# Open_EVI.net
KiCad netlist of a schematic drawn in EAGLE
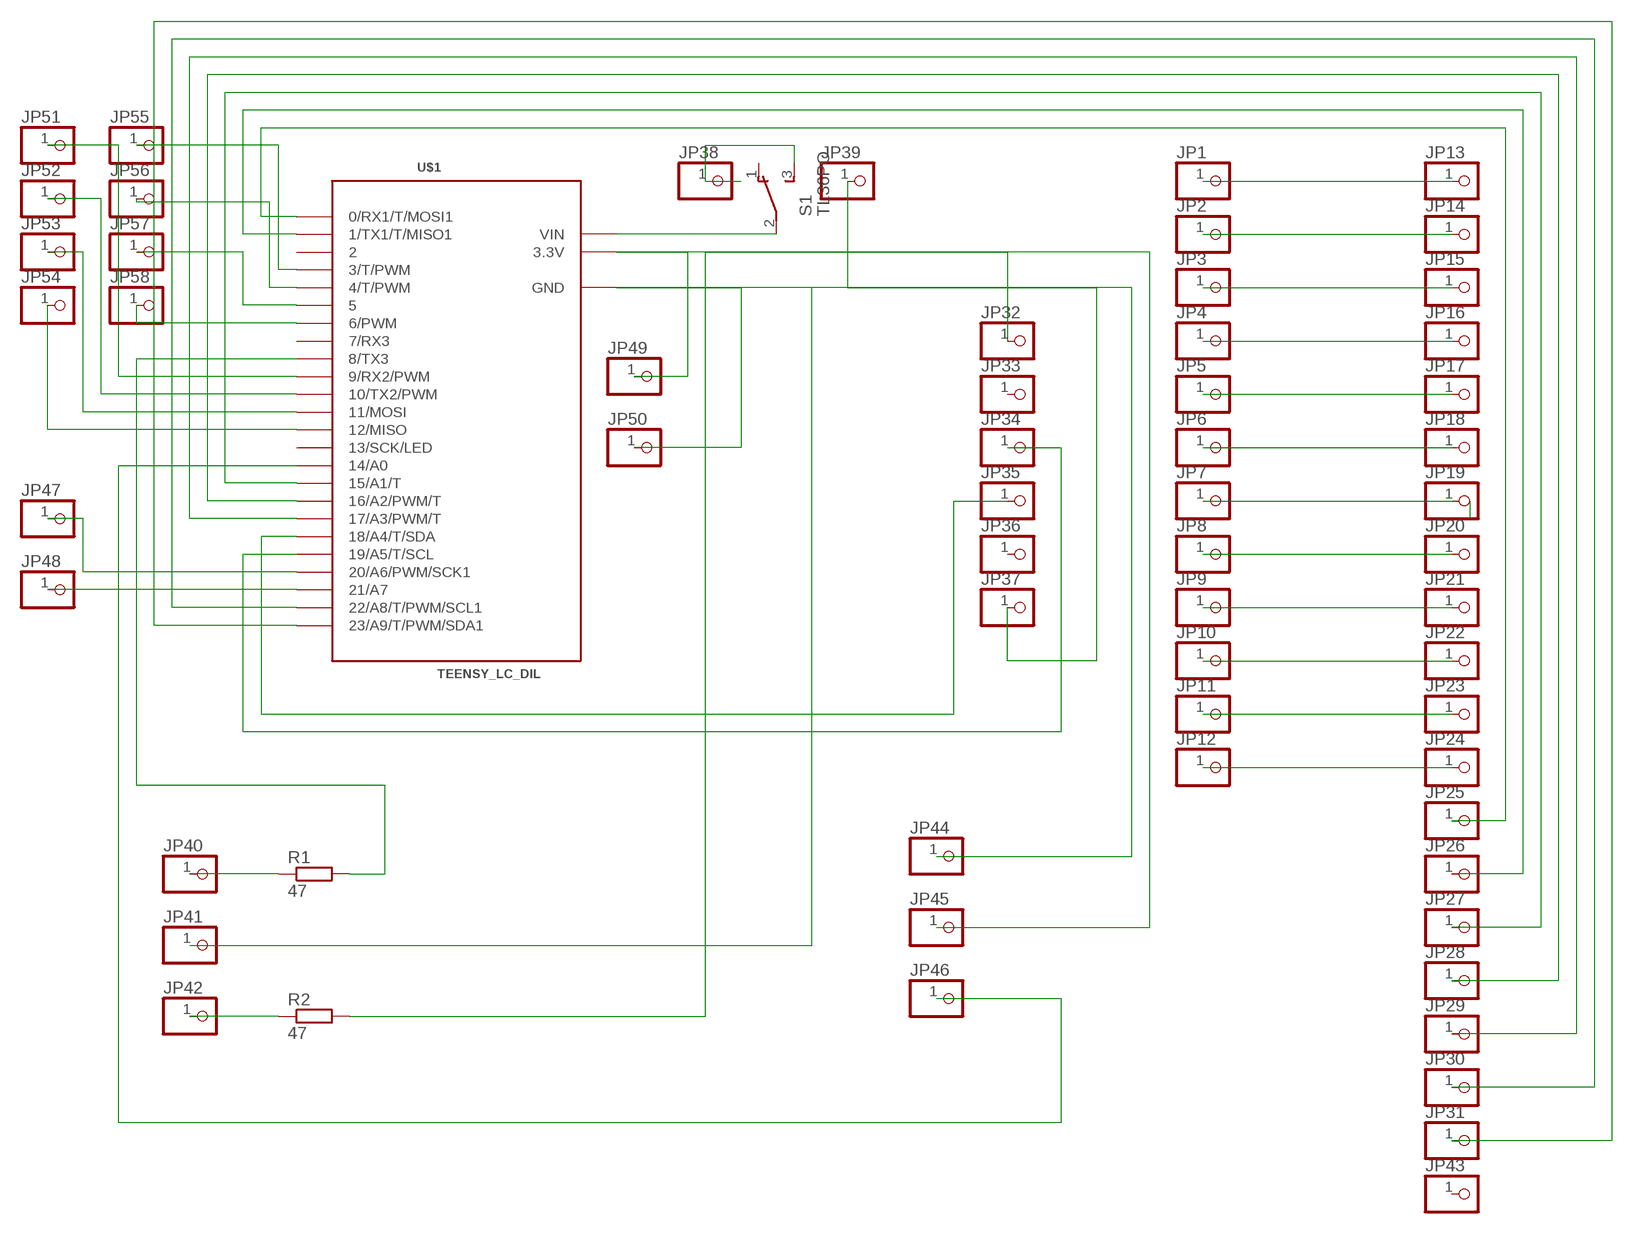
[diagram p0: schematic, sheet 1]

(export (version "E")
  (design (tool "Eeschema 10.0.6"))
  (components
    (comp (ref "JP1")
      (value "PINHD-1X1")
      (footprint "eagle-import:1X01")
      (libsource (lib "eagle-import") (part "PINHD-1X1"))
    )
    (comp (ref "JP2")
      (value "PINHD-1X1")
      (footprint "eagle-import:1X01")
      (libsource (lib "eagle-import") (part "PINHD-1X1"))
    )
    (comp (ref "JP3")
      (value "PINHD-1X1")
      (footprint "eagle-import:1X01")
      (libsource (lib "eagle-import") (part "PINHD-1X1"))
    )
    (comp (ref "JP4")
      (value "PINHD-1X1")
      (footprint "eagle-import:1X01")
      (libsource (lib "eagle-import") (part "PINHD-1X1"))
    )
    (comp (ref "JP5")
      (value "PINHD-1X1")
      (footprint "eagle-import:1X01")
      (libsource (lib "eagle-import") (part "PINHD-1X1"))
    )
    (comp (ref "JP6")
      (value "PINHD-1X1")
      (footprint "eagle-import:1X01")
      (libsource (lib "eagle-import") (part "PINHD-1X1"))
    )
    (comp (ref "JP7")
      (value "PINHD-1X1")
      (footprint "eagle-import:1X01")
      (libsource (lib "eagle-import") (part "PINHD-1X1"))
    )
    (comp (ref "JP8")
      (value "PINHD-1X1")
      (footprint "eagle-import:1X01")
      (libsource (lib "eagle-import") (part "PINHD-1X1"))
    )
    (comp (ref "JP9")
      (value "PINHD-1X1")
      (footprint "eagle-import:1X01")
      (libsource (lib "eagle-import") (part "PINHD-1X1"))
    )
    (comp (ref "JP10")
      (value "PINHD-1X1")
      (footprint "eagle-import:1X01")
      (libsource (lib "eagle-import") (part "PINHD-1X1"))
    )
    (comp (ref "JP11")
      (value "PINHD-1X1")
      (footprint "eagle-import:1X01")
      (libsource (lib "eagle-import") (part "PINHD-1X1"))
    )
    (comp (ref "JP12")
      (value "PINHD-1X1")
      (footprint "eagle-import:1X01")
      (libsource (lib "eagle-import") (part "PINHD-1X1"))
    )
    (comp (ref "JP13")
      (value "PINHD-1X1")
      (footprint "eagle-import:1X01")
      (libsource (lib "eagle-import") (part "PINHD-1X1"))
    )
    (comp (ref "JP14")
      (value "PINHD-1X1")
      (footprint "eagle-import:1X01")
      (libsource (lib "eagle-import") (part "PINHD-1X1"))
    )
    (comp (ref "JP15")
      (value "PINHD-1X1")
      (footprint "eagle-import:1X01")
      (libsource (lib "eagle-import") (part "PINHD-1X1"))
    )
    (comp (ref "JP16")
      (value "PINHD-1X1")
      (footprint "eagle-import:1X01")
      (libsource (lib "eagle-import") (part "PINHD-1X1"))
    )
    (comp (ref "JP17")
      (value "PINHD-1X1")
      (footprint "eagle-import:1X01")
      (libsource (lib "eagle-import") (part "PINHD-1X1"))
    )
    (comp (ref "JP18")
      (value "PINHD-1X1")
      (footprint "eagle-import:1X01")
      (libsource (lib "eagle-import") (part "PINHD-1X1"))
    )
    (comp (ref "JP19")
      (value "PINHD-1X1")
      (footprint "eagle-import:1X01")
      (libsource (lib "eagle-import") (part "PINHD-1X1"))
    )
    (comp (ref "JP20")
      (value "PINHD-1X1")
      (footprint "eagle-import:1X01")
      (libsource (lib "eagle-import") (part "PINHD-1X1"))
    )
    (comp (ref "JP21")
      (value "PINHD-1X1")
      (footprint "eagle-import:1X01")
      (libsource (lib "eagle-import") (part "PINHD-1X1"))
    )
    (comp (ref "JP22")
      (value "PINHD-1X1")
      (footprint "eagle-import:1X01")
      (libsource (lib "eagle-import") (part "PINHD-1X1"))
    )
    (comp (ref "JP23")
      (value "PINHD-1X1")
      (footprint "eagle-import:1X01")
      (libsource (lib "eagle-import") (part "PINHD-1X1"))
    )
    (comp (ref "JP24")
      (value "PINHD-1X1")
      (footprint "eagle-import:1X01")
      (libsource (lib "eagle-import") (part "PINHD-1X1"))
    )
    (comp (ref "JP25")
      (value "PINHD-1X1")
      (footprint "eagle-import:1X01")
      (libsource (lib "eagle-import") (part "PINHD-1X1"))
    )
    (comp (ref "JP26")
      (value "PINHD-1X1")
      (footprint "eagle-import:1X01")
      (libsource (lib "eagle-import") (part "PINHD-1X1"))
    )
    (comp (ref "JP27")
      (value "PINHD-1X1")
      (footprint "eagle-import:1X01")
      (libsource (lib "eagle-import") (part "PINHD-1X1"))
    )
    (comp (ref "JP28")
      (value "PINHD-1X1")
      (footprint "eagle-import:1X01")
      (libsource (lib "eagle-import") (part "PINHD-1X1"))
    )
    (comp (ref "JP29")
      (value "PINHD-1X1")
      (footprint "eagle-import:1X01")
      (libsource (lib "eagle-import") (part "PINHD-1X1"))
    )
    (comp (ref "JP30")
      (value "PINHD-1X1")
      (footprint "eagle-import:1X01")
      (libsource (lib "eagle-import") (part "PINHD-1X1"))
    )
    (comp (ref "JP31")
      (value "PINHD-1X1")
      (footprint "eagle-import:1X01")
      (libsource (lib "eagle-import") (part "PINHD-1X1"))
    )
    (comp (ref "JP32")
      (value "PINHD-1X1")
      (footprint "eagle-import:1X01")
      (libsource (lib "eagle-import") (part "PINHD-1X1"))
    )
    (comp (ref "JP33")
      (value "PINHD-1X1")
      (footprint "eagle-import:1X01")
      (libsource (lib "eagle-import") (part "PINHD-1X1"))
    )
    (comp (ref "JP34")
      (value "PINHD-1X1")
      (footprint "eagle-import:1X01")
      (libsource (lib "eagle-import") (part "PINHD-1X1"))
    )
    (comp (ref "JP35")
      (value "PINHD-1X1")
      (footprint "eagle-import:1X01")
      (libsource (lib "eagle-import") (part "PINHD-1X1"))
    )
    (comp (ref "JP36")
      (value "PINHD-1X1")
      (footprint "eagle-import:1X01")
      (libsource (lib "eagle-import") (part "PINHD-1X1"))
    )
    (comp (ref "JP37")
      (value "PINHD-1X1")
      (footprint "eagle-import:1X01")
      (libsource (lib "eagle-import") (part "PINHD-1X1"))
    )
    (comp (ref "JP38")
      (value "PINHD-1X1")
      (footprint "eagle-import:1X01")
      (libsource (lib "eagle-import") (part "PINHD-1X1"))
    )
    (comp (ref "JP39")
      (value "PINHD-1X1")
      (footprint "eagle-import:1X01")
      (libsource (lib "eagle-import") (part "PINHD-1X1"))
    )
    (comp (ref "JP40")
      (value "PINHD-1X1")
      (footprint "eagle-import:1X01")
      (libsource (lib "eagle-import") (part "PINHD-1X1"))
    )
    (comp (ref "JP41")
      (value "PINHD-1X1")
      (footprint "eagle-import:1X01")
      (libsource (lib "eagle-import") (part "PINHD-1X1"))
    )
    (comp (ref "JP42")
      (value "PINHD-1X1")
      (footprint "eagle-import:1X01")
      (libsource (lib "eagle-import") (part "PINHD-1X1"))
    )
    (comp (ref "JP43")
      (value "PINHD-1X1")
      (footprint "eagle-import:1X01")
      (libsource (lib "eagle-import") (part "PINHD-1X1"))
    )
    (comp (ref "JP44")
      (value "PINHD-1X1")
      (footprint "eagle-import:1X01")
      (libsource (lib "eagle-import") (part "PINHD-1X1"))
    )
    (comp (ref "JP45")
      (value "PINHD-1X1")
      (footprint "eagle-import:1X01")
      (libsource (lib "eagle-import") (part "PINHD-1X1"))
    )
    (comp (ref "JP46")
      (value "PINHD-1X1")
      (footprint "eagle-import:1X01")
      (libsource (lib "eagle-import") (part "PINHD-1X1"))
    )
    (comp (ref "JP47")
      (value "PINHD-1X1")
      (footprint "eagle-import:1X01")
      (libsource (lib "eagle-import") (part "PINHD-1X1"))
    )
    (comp (ref "JP48")
      (value "PINHD-1X1")
      (footprint "eagle-import:1X01")
      (libsource (lib "eagle-import") (part "PINHD-1X1"))
    )
    (comp (ref "JP49")
      (value "PINHD-1X1")
      (footprint "eagle-import:1X01")
      (libsource (lib "eagle-import") (part "PINHD-1X1"))
    )
    (comp (ref "JP50")
      (value "PINHD-1X1")
      (footprint "eagle-import:1X01")
      (libsource (lib "eagle-import") (part "PINHD-1X1"))
    )
    (comp (ref "JP51")
      (value "PINHD-1X1")
      (footprint "eagle-import:1X01")
      (libsource (lib "eagle-import") (part "PINHD-1X1"))
    )
    (comp (ref "JP52")
      (value "PINHD-1X1")
      (footprint "eagle-import:1X01")
      (libsource (lib "eagle-import") (part "PINHD-1X1"))
    )
    (comp (ref "JP53")
      (value "PINHD-1X1")
      (footprint "eagle-import:1X01")
      (libsource (lib "eagle-import") (part "PINHD-1X1"))
    )
    (comp (ref "JP54")
      (value "PINHD-1X1")
      (footprint "eagle-import:1X01")
      (libsource (lib "eagle-import") (part "PINHD-1X1"))
    )
    (comp (ref "JP55")
      (value "PINHD-1X1")
      (footprint "eagle-import:1X01")
      (libsource (lib "eagle-import") (part "PINHD-1X1"))
    )
    (comp (ref "JP56")
      (value "PINHD-1X1")
      (footprint "eagle-import:1X01")
      (libsource (lib "eagle-import") (part "PINHD-1X1"))
    )
    (comp (ref "JP57")
      (value "PINHD-1X1")
      (footprint "eagle-import:1X01")
      (libsource (lib "eagle-import") (part "PINHD-1X1"))
    )
    (comp (ref "JP58")
      (value "PINHD-1X1")
      (footprint "eagle-import:1X01")
      (libsource (lib "eagle-import") (part "PINHD-1X1"))
    )
    (comp (ref "R1")
      (value "47")
      (footprint "eagle-import:0207_7")
      (libsource (lib "eagle-import") (part "R-EU_0207/7"))
    )
    (comp (ref "R2")
      (value "47")
      (footprint "eagle-import:0207_7")
      (libsource (lib "eagle-import") (part "R-EU_0207/7"))
    )
    (comp (ref "S1")
      (value "TL36PO")
      (footprint "eagle-import:TL3XPO")
      (libsource (lib "eagle-import") (part "TL36PO"))
    )
    (comp (ref "U$1")
      (value "TEENSY_LC_DIL")
      (footprint "eagle-import:TEENSY_3.0-3.2&LC_DIL")
      (libsource (lib "eagle-import") (part "TEENSY_LC_DIL"))
    )
  )
  (nets
    (net (code "1") (name "Net-(JP1-Pad1)") (class "Default")
      (node (ref "JP1") (pin "1") (pinfunction "1_1") (pintype "passive"))
      (node (ref "JP13") (pin "1") (pinfunction "1_1") (pintype "passive"))
    )
    (net (code "2") (name "Net-(JP10-Pad1)") (class "Default")
      (node (ref "JP10") (pin "1") (pinfunction "1_1") (pintype "passive"))
      (node (ref "JP22") (pin "1") (pinfunction "1_1") (pintype "passive"))
    )
    (net (code "3") (name "Net-(JP11-Pad1)") (class "Default")
      (node (ref "JP11") (pin "1") (pinfunction "1_1") (pintype "passive"))
      (node (ref "JP23") (pin "1") (pinfunction "1_1") (pintype "passive"))
    )
    (net (code "4") (name "Net-(JP12-Pad1)") (class "Default")
      (node (ref "JP12") (pin "1") (pinfunction "1_1") (pintype "passive"))
      (node (ref "JP24") (pin "1") (pinfunction "1_1") (pintype "passive"))
    )
    (net (code "5") (name "Net-(JP14-Pad1)") (class "Default")
      (node (ref "JP14") (pin "1") (pinfunction "1_1") (pintype "passive"))
      (node (ref "JP2") (pin "1") (pinfunction "1_1") (pintype "passive"))
    )
    (net (code "6") (name "Net-(JP15-Pad1)") (class "Default")
      (node (ref "JP15") (pin "1") (pinfunction "1_1") (pintype "passive"))
      (node (ref "JP3") (pin "1") (pinfunction "1_1") (pintype "passive"))
    )
    (net (code "7") (name "Net-(JP16-Pad1)") (class "Default")
      (node (ref "JP16") (pin "1") (pinfunction "1_1") (pintype "passive"))
      (node (ref "JP4") (pin "1") (pinfunction "1_1") (pintype "passive"))
    )
    (net (code "8") (name "Net-(JP17-Pad1)") (class "Default")
      (node (ref "JP17") (pin "1") (pinfunction "1_1") (pintype "passive"))
      (node (ref "JP5") (pin "1") (pinfunction "1_1") (pintype "passive"))
    )
    (net (code "9") (name "Net-(JP18-Pad1)") (class "Default")
      (node (ref "JP18") (pin "1") (pinfunction "1_1") (pintype "passive"))
      (node (ref "JP6") (pin "1") (pinfunction "1_1") (pintype "passive"))
    )
    (net (code "10") (name "Net-(JP19-Pad1)") (class "Default")
      (node (ref "JP19") (pin "1") (pinfunction "1_1") (pintype "passive"))
      (node (ref "JP7") (pin "1") (pinfunction "1_1") (pintype "passive"))
    )
    (net (code "11") (name "Net-(JP20-Pad1)") (class "Default")
      (node (ref "JP20") (pin "1") (pinfunction "1_1") (pintype "passive"))
      (node (ref "JP8") (pin "1") (pinfunction "1_1") (pintype "passive"))
    )
    (net (code "12") (name "Net-(JP21-Pad1)") (class "Default")
      (node (ref "JP21") (pin "1") (pinfunction "1_1") (pintype "passive"))
      (node (ref "JP9") (pin "1") (pinfunction "1_1") (pintype "passive"))
    )
    (net (code "13") (name "Net-(JP32-Pad1)") (class "Default")
      (node (ref "JP32") (pin "1") (pinfunction "1_1") (pintype "passive"))
      (node (ref "JP45") (pin "1") (pinfunction "1_1") (pintype "passive"))
      (node (ref "JP49") (pin "1") (pinfunction "1_1") (pintype "passive"))
      (node (ref "R2") (pin "2") (pinfunction "2_2") (pintype "passive"))
      (node (ref "U$1") (pin "3.3V") (pinfunction "3.3V_3.3V") (pintype "power_in"))
    )
    (net (code "14") (name "Net-(JP37-Pad1)") (class "Default")
      (node (ref "JP37") (pin "1") (pinfunction "1_1") (pintype "passive"))
      (node (ref "JP39") (pin "1") (pinfunction "1_1") (pintype "passive"))
      (node (ref "JP41") (pin "1") (pinfunction "1_1") (pintype "passive"))
      (node (ref "JP44") (pin "1") (pinfunction "1_1") (pintype "passive"))
      (node (ref "JP50") (pin "1") (pinfunction "1_1") (pintype "passive"))
      (node (ref "U$1") (pin "AGND") (pinfunction "GND_AGND") (pintype "power_in"))
      (node (ref "U$1") (pin "GND") (pinfunction "GND_GND") (pintype "power_in"))
    )
    (net (code "15") (name "Net-(JP40-Pad1)") (class "Default")
      (node (ref "JP40") (pin "1") (pinfunction "1_1") (pintype "passive"))
      (node (ref "R1") (pin "1") (pinfunction "1_1") (pintype "passive"))
    )
    (net (code "16") (name "Net-(JP42-Pad1)") (class "Default")
      (node (ref "JP42") (pin "1") (pinfunction "1_1") (pintype "passive"))
      (node (ref "R2") (pin "1") (pinfunction "1_1") (pintype "passive"))
    )
    (net (code "17") (name "Net-(JP46-Pad1)") (class "Default")
      (node (ref "JP46") (pin "1") (pinfunction "1_1") (pintype "passive"))
      (node (ref "U$1") (pin "14/A0") (pinfunction "14/A0_14/A0") (pintype "bidirectional"))
    )
    (net (code "18") (name "Net-(JP48-Pad1)") (class "Default")
      (node (ref "JP48") (pin "1") (pinfunction "1_1") (pintype "passive"))
      (node (ref "U$1") (pin "21/A7") (pinfunction "21/A7_21/A7") (pintype "bidirectional"))
    )
    (net (code "19") (name "Net-(JP57-Pad1)") (class "Default")
      (node (ref "JP57") (pin "1") (pinfunction "1_1") (pintype "passive"))
      (node (ref "U$1") (pin "5") (pinfunction "5_5") (pintype "bidirectional"))
    )
    (net (code "20") (name "Net-(S1-P)") (class "Default")
      (node (ref "S1") (pin "2") (pinfunction "P_2") (pintype "passive"))
      (node (ref "U$1") (pin "VIN") (pinfunction "VIN_VIN") (pintype "power_in"))
    )
    (net (code "21") (name "Net-(S1-S)") (class "Default")
      (node (ref "JP38") (pin "1") (pinfunction "1_1") (pintype "passive"))
      (node (ref "S1") (pin "3") (pinfunction "S_3") (pintype "passive"))
    )
    (net (code "22") (name "Net-(U$1-0{slash}RX1{slash}T{slash}MOSI1)") (class "Default")
      (node (ref "JP25") (pin "1") (pinfunction "1_1") (pintype "passive"))
      (node (ref "U$1") (pin "0") (pinfunction "0/RX1/T/MOSI1_0") (pintype "bidirectional"))
    )
    (net (code "23") (name "Net-(U$1-1{slash}TX1{slash}T{slash}MISO1)") (class "Default")
      (node (ref "JP26") (pin "1") (pinfunction "1_1") (pintype "passive"))
      (node (ref "U$1") (pin "1") (pinfunction "1/TX1/T/MISO1_1") (pintype "bidirectional"))
    )
    (net (code "24") (name "Net-(U$1-3{slash}T{slash}PWM)") (class "Default")
      (node (ref "JP55") (pin "1") (pinfunction "1_1") (pintype "passive"))
      (node (ref "U$1") (pin "3") (pinfunction "3/T/PWM_3") (pintype "bidirectional"))
    )
    (net (code "25") (name "Net-(U$1-4{slash}T{slash}PWM)") (class "Default")
      (node (ref "JP56") (pin "1") (pinfunction "1_1") (pintype "passive"))
      (node (ref "U$1") (pin "4") (pinfunction "4/T/PWM_4") (pintype "bidirectional"))
    )
    (net (code "26") (name "Net-(U$1-6{slash}PWM)") (class "Default")
      (node (ref "JP58") (pin "1") (pinfunction "1_1") (pintype "passive"))
      (node (ref "U$1") (pin "6") (pinfunction "6/PWM_6") (pintype "bidirectional"))
    )
    (net (code "27") (name "Net-(U$1-8{slash}TX3)") (class "Default")
      (node (ref "R1") (pin "2") (pinfunction "2_2") (pintype "passive"))
      (node (ref "U$1") (pin "8") (pinfunction "8/TX3_8") (pintype "bidirectional"))
    )
    (net (code "28") (name "Net-(U$1-9{slash}RX2{slash}PWM)") (class "Default")
      (node (ref "JP51") (pin "1") (pinfunction "1_1") (pintype "passive"))
      (node (ref "U$1") (pin "9") (pinfunction "9/RX2/PWM_9") (pintype "bidirectional"))
    )
    (net (code "29") (name "Net-(U$1-10{slash}TX2{slash}PWM)") (class "Default")
      (node (ref "JP52") (pin "1") (pinfunction "1_1") (pintype "passive"))
      (node (ref "U$1") (pin "10") (pinfunction "10/TX2/PWM_10") (pintype "bidirectional"))
    )
    (net (code "30") (name "Net-(U$1-11{slash}MOSI)") (class "Default")
      (node (ref "JP53") (pin "1") (pinfunction "1_1") (pintype "passive"))
      (node (ref "U$1") (pin "11") (pinfunction "11/MOSI_11") (pintype "bidirectional"))
    )
    (net (code "31") (name "Net-(U$1-12{slash}MISO)") (class "Default")
      (node (ref "JP54") (pin "1") (pinfunction "1_1") (pintype "passive"))
      (node (ref "U$1") (pin "12") (pinfunction "12/MISO_12") (pintype "bidirectional"))
    )
    (net (code "32") (name "Net-(U$1-15{slash}A1{slash}T)") (class "Default")
      (node (ref "JP27") (pin "1") (pinfunction "1_1") (pintype "passive"))
      (node (ref "U$1") (pin "15/A1") (pinfunction "15/A1/T_15/A1") (pintype "bidirectional"))
    )
    (net (code "33") (name "Net-(U$1-16{slash}A2{slash}PWM{slash}T)") (class "Default")
      (node (ref "JP28") (pin "1") (pinfunction "1_1") (pintype "passive"))
      (node (ref "U$1") (pin "16/A2") (pinfunction "16/A2/PWM/T_16/A2") (pintype "bidirectional"))
    )
    (net (code "34") (name "Net-(U$1-17{slash}A3{slash}PWM{slash}T)") (class "Default")
      (node (ref "JP29") (pin "1") (pinfunction "1_1") (pintype "passive"))
      (node (ref "U$1") (pin "17/A3") (pinfunction "17/A3/PWM/T_17/A3") (pintype "bidirectional"))
    )
    (net (code "35") (name "Net-(U$1-18{slash}A4{slash}T{slash}SDA)") (class "Default")
      (node (ref "JP35") (pin "1") (pinfunction "1_1") (pintype "passive"))
      (node (ref "U$1") (pin "18/A4") (pinfunction "18/A4/T/SDA_18/A4") (pintype "bidirectional"))
    )
    (net (code "36") (name "Net-(U$1-19{slash}A5{slash}T{slash}SCL)") (class "Default")
      (node (ref "JP34") (pin "1") (pinfunction "1_1") (pintype "passive"))
      (node (ref "U$1") (pin "19/A5") (pinfunction "19/A5/T/SCL_19/A5") (pintype "bidirectional"))
    )
    (net (code "37") (name "Net-(U$1-20{slash}A6{slash}PWM{slash}SCK1)") (class "Default")
      (node (ref "JP47") (pin "1") (pinfunction "1_1") (pintype "passive"))
      (node (ref "U$1") (pin "20/A6") (pinfunction "20/A6/PWM/SCK1_20/A6") (pintype "bidirectional"))
    )
    (net (code "38") (name "Net-(U$1-22{slash}A8{slash}T{slash}PWM{slash}SCL1)") (class "Default")
      (node (ref "JP30") (pin "1") (pinfunction "1_1") (pintype "passive"))
      (node (ref "U$1") (pin "22/A8") (pinfunction "22/A8/T/PWM/SCL1_22/A8") (pintype "bidirectional"))
    )
    (net (code "39") (name "Net-(U$1-23{slash}A9{slash}T{slash}PWM{slash}SDA1)") (class "Default")
      (node (ref "JP31") (pin "1") (pinfunction "1_1") (pintype "passive"))
      (node (ref "U$1") (pin "23/A9") (pinfunction "23/A9/T/PWM/SDA1_23/A9") (pintype "bidirectional"))
    )
    (net (code "40") (name "unconnected-(JP33-Pad1)") (class "Default")
      (node (ref "JP33") (pin "1") (pinfunction "1_1") (pintype "passive"))
    )
    (net (code "41") (name "unconnected-(JP36-Pad1)") (class "Default")
      (node (ref "JP36") (pin "1") (pinfunction "1_1") (pintype "passive"))
    )
    (net (code "42") (name "unconnected-(JP43-Pad1)") (class "Default")
      (node (ref "JP43") (pin "1") (pinfunction "1_1") (pintype "passive"))
    )
    (net (code "43") (name "unconnected-(S1-O-Pad1)") (class "Default")
      (node (ref "S1") (pin "1") (pinfunction "O_1") (pintype "passive"))
    )
    (net (code "44") (name "unconnected-(U$1-7{slash}RX3-Pad7)") (class "Default")
      (node (ref "U$1") (pin "7") (pinfunction "7/RX3_7") (pintype "bidirectional"))
    )
    (net (code "45") (name "unconnected-(U$1-13{slash}SCK{slash}LED-Pad13)") (class "Default")
      (node (ref "U$1") (pin "13") (pinfunction "13/SCK/LED_13") (pintype "bidirectional"))
    )
    (net (code "46") (name "unconnected-(U$1-Pad2)") (class "Default")
      (node (ref "U$1") (pin "2") (pinfunction "2_2") (pintype "bidirectional"))
    )
  )
)
